# SDuino_ultramicroOLED_Dual.net
KiCad netlist of a schematic drawn in EAGLE
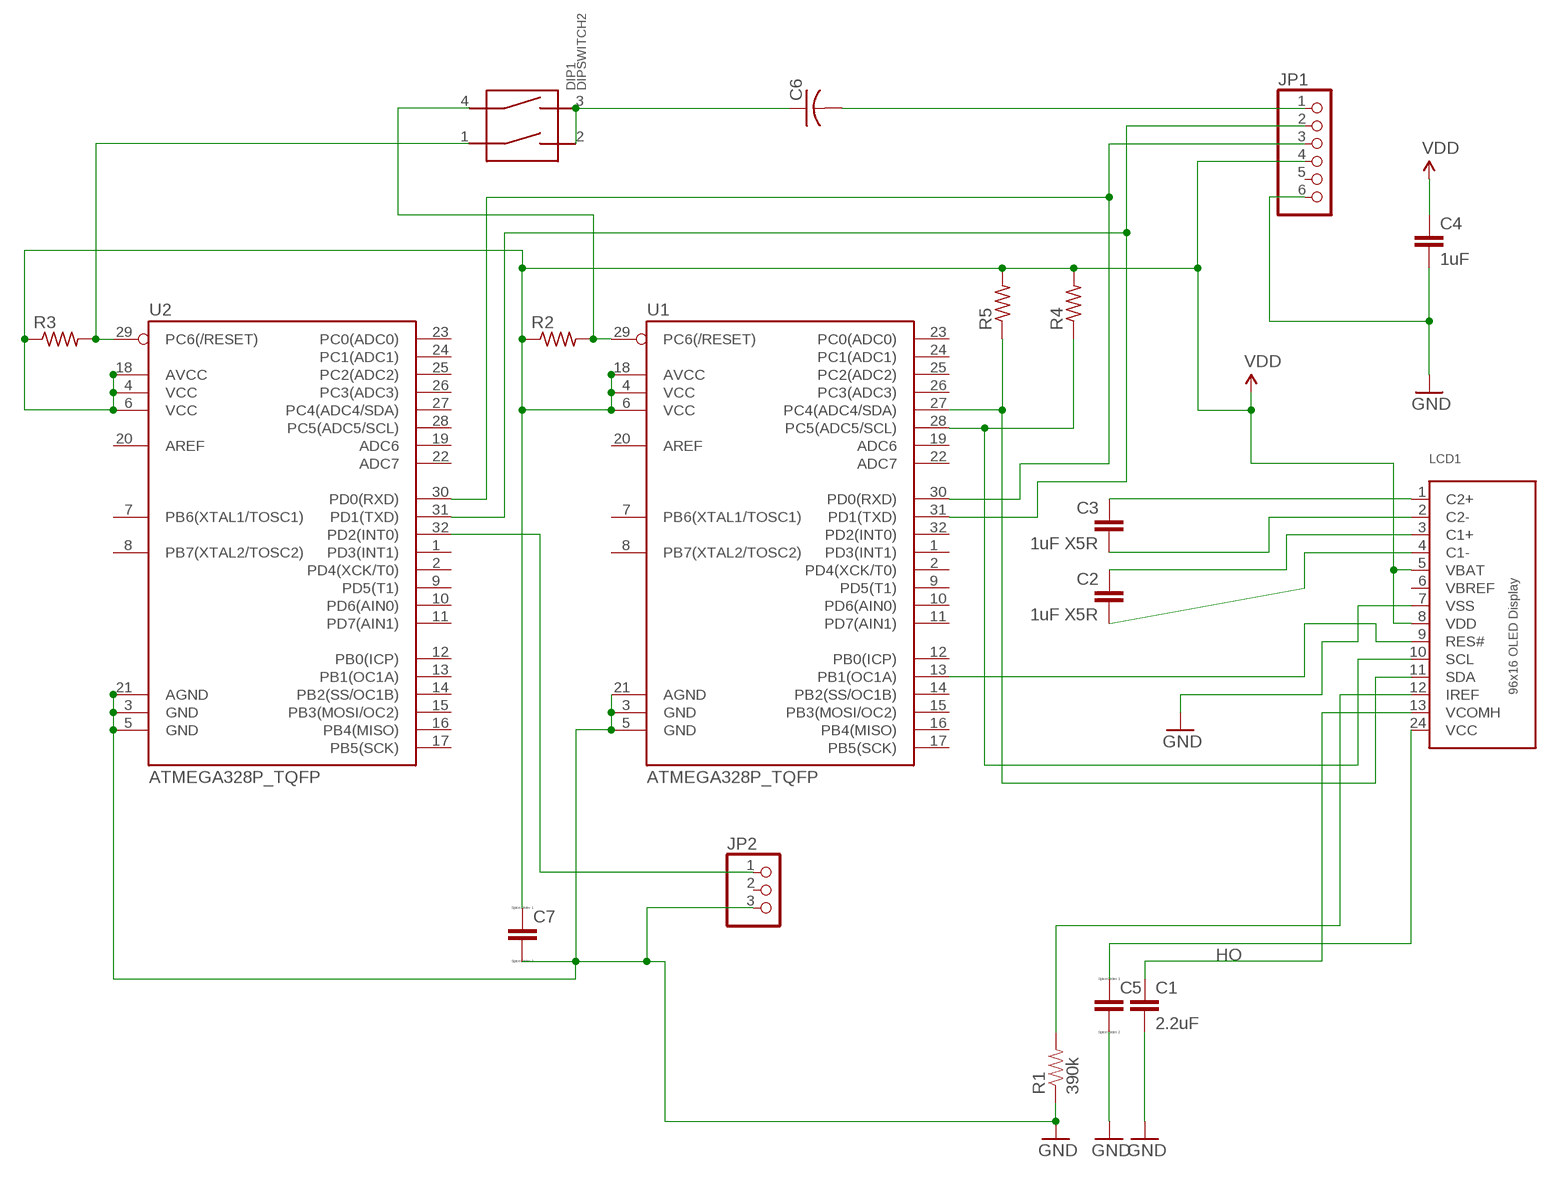
[diagram p0: schematic, sheet 1]

(export (version "E")
  (design (tool "Eeschema 10.0.6"))
  (components
    (comp (ref "C1")
      (value "2.2uF")
      (footprint "eagle-import:0805")
      (libsource (lib "eagle-import") (part "CAP0805"))
    )
    (comp (ref "C2")
      (value "1uF X5R")
      (footprint "eagle-import:0805")
      (libsource (lib "eagle-import") (part "CAP0805"))
    )
    (comp (ref "C3")
      (value "1uF X5R")
      (footprint "eagle-import:0805")
      (libsource (lib "eagle-import") (part "CAP0805"))
    )
    (comp (ref "C4")
      (value "1uF")
      (footprint "eagle-import:0603-CAP")
      (libsource (lib "eagle-import") (part "CAP0603-CAP"))
    )
    (comp (ref "C5")
      (value "CC0603")
      (footprint "eagle-import:C0603")
      (libsource (lib "eagle-import") (part "CC0603"))
    )
    (comp (ref "C6")
      (value "C-USC0603K")
      (footprint "eagle-import:C0603K")
      (libsource (lib "eagle-import") (part "C-USC0603K"))
    )
    (comp (ref "C7")
      (value "CC0603")
      (footprint "eagle-import:C0603")
      (libsource (lib "eagle-import") (part "CC0603"))
    )
    (comp (ref "DIP1")
      (value "DIPSWITCH2")
      (footprint "eagle-import:DIPSWITCH2")
      (libsource (lib "eagle-import") (part "DIPSWITCH2"))
    )
    (comp (ref "JP1")
      (value "HEADER-1X6")
      (footprint "eagle-import:1X06_OVAL")
      (libsource (lib "eagle-import") (part "HEADER-1X6"))
    )
    (comp (ref "JP2")
      (value "HEADER-1X3")
      (footprint "eagle-import:1X03_OVAL")
      (libsource (lib "eagle-import") (part "HEADER-1X3"))
    )
    (comp (ref "LCD1")
      (value "DISP_OLED_UG-9616GLBBG02")
      (footprint "eagle-import:UG-9616GLBBG02_0.65MM_WRAPAROUND")
      (libsource (lib "eagle-import") (part "DISP_OLED_UG-9616GLBBG02"))
    )
    (comp (ref "R1")
      (value "390k")
      (footprint "eagle-import:0603-RES")
      (libsource (lib "eagle-import") (part "RESISTOR0603-RES"))
    )
    (comp (ref "R2")
      (value "R-US_R0603")
      (footprint "eagle-import:R0603")
      (libsource (lib "eagle-import") (part "R-US_R0603"))
    )
    (comp (ref "R3")
      (value "R-US_R0603")
      (footprint "eagle-import:R0603")
      (libsource (lib "eagle-import") (part "R-US_R0603"))
    )
    (comp (ref "R4")
      (value "R-US_R0603")
      (footprint "eagle-import:R0603")
      (libsource (lib "eagle-import") (part "R-US_R0603"))
    )
    (comp (ref "R5")
      (value "R-US_R0603")
      (footprint "eagle-import:R0603")
      (libsource (lib "eagle-import") (part "R-US_R0603"))
    )
    (comp (ref "U1")
      (value "ATMEGA328P_TQFP")
      (footprint "eagle-import:TQFP32-08")
      (libsource (lib "eagle-import") (part "ATMEGA328P_TQFP"))
    )
    (comp (ref "U2")
      (value "ATMEGA328P_TQFP")
      (footprint "eagle-import:TQFP32-08")
      (libsource (lib "eagle-import") (part "ATMEGA328P_TQFP"))
    )
  )
  (nets
    (net (code "1") (name "/HO") (class "Default")
      (node (ref "C1") (pin "1") (pinfunction "1_1") (pintype "passive"))
      (node (ref "LCD1") (pin "13") (pinfunction "VCOMH_13") (pintype "bidirectional"))
    )
    (net (code "2") (name "GND") (class "Default")
      (node (ref "C1") (pin "2") (pinfunction "2_2") (pintype "passive"))
      (node (ref "C4") (pin "2") (pinfunction "2_2") (pintype "passive"))
      (node (ref "C5") (pin "2") (pinfunction "2_2") (pintype "passive"))
      (node (ref "C7") (pin "2") (pinfunction "2_2") (pintype "passive"))
      (node (ref "JP1") (pin "6") (pinfunction "6_6") (pintype "passive"))
      (node (ref "JP2") (pin "3") (pinfunction "3_3") (pintype "passive"))
      (node (ref "LCD1") (pin "7") (pinfunction "VSS_7") (pintype "bidirectional"))
      (node (ref "R1") (pin "1") (pinfunction "1_1") (pintype "passive"))
      (node (ref "U1") (pin "21") (pinfunction "AGND_21") (pintype "bidirectional"))
      (node (ref "U1") (pin "3") (pinfunction "GND_3") (pintype "bidirectional"))
      (node (ref "U1") (pin "5") (pinfunction "GND_5") (pintype "bidirectional"))
      (node (ref "U2") (pin "21") (pinfunction "AGND_21") (pintype "bidirectional"))
      (node (ref "U2") (pin "3") (pinfunction "GND_3") (pintype "bidirectional"))
      (node (ref "U2") (pin "5") (pinfunction "GND_5") (pintype "bidirectional"))
    )
    (net (code "3") (name "Net-(C6-Pad2)") (class "Default")
      (node (ref "C6") (pin "2") (pinfunction "2_2") (pintype "passive"))
      (node (ref "JP1") (pin "1") (pinfunction "1_1") (pintype "passive"))
    )
    (net (code "4") (name "Net-(DIP1-P$1)") (class "Default")
      (node (ref "DIP1") (pin "1") (pinfunction "P$1_1") (pintype "bidirectional"))
      (node (ref "R3") (pin "2") (pinfunction "2_2") (pintype "passive"))
      (node (ref "U2") (pin "29") (pinfunction "PC6(/RESET)_29") (pintype "bidirectional"))
    )
    (net (code "5") (name "Net-(DIP1-P$2)") (class "Default")
      (node (ref "C6") (pin "1") (pinfunction "1_1") (pintype "passive"))
      (node (ref "DIP1") (pin "2") (pinfunction "P$2_2") (pintype "bidirectional"))
      (node (ref "DIP1") (pin "3") (pinfunction "P$3_3") (pintype "bidirectional"))
    )
    (net (code "6") (name "Net-(DIP1-P$4)") (class "Default")
      (node (ref "DIP1") (pin "4") (pinfunction "P$4_4") (pintype "bidirectional"))
      (node (ref "R2") (pin "2") (pinfunction "2_2") (pintype "passive"))
      (node (ref "U1") (pin "29") (pinfunction "PC6(/RESET)_29") (pintype "bidirectional"))
    )
    (net (code "7") (name "Net-(LCD1-C1+)") (class "Default")
      (node (ref "C2") (pin "1") (pinfunction "1_1") (pintype "passive"))
      (node (ref "LCD1") (pin "3") (pinfunction "C1+_3") (pintype "bidirectional"))
    )
    (net (code "8") (name "Net-(LCD1-C1-)") (class "Default")
      (node (ref "C2") (pin "2") (pinfunction "2_2") (pintype "passive"))
      (node (ref "LCD1") (pin "4") (pinfunction "C1-_4") (pintype "bidirectional"))
    )
    (net (code "9") (name "Net-(LCD1-C2+)") (class "Default")
      (node (ref "C3") (pin "1") (pinfunction "1_1") (pintype "passive"))
      (node (ref "LCD1") (pin "1") (pinfunction "C2+_1") (pintype "bidirectional"))
    )
    (net (code "10") (name "Net-(LCD1-C2-)") (class "Default")
      (node (ref "C3") (pin "2") (pinfunction "2_2") (pintype "passive"))
      (node (ref "LCD1") (pin "2") (pinfunction "C2-_2") (pintype "bidirectional"))
    )
    (net (code "11") (name "Net-(LCD1-IREF)") (class "Default")
      (node (ref "LCD1") (pin "12") (pinfunction "IREF_12") (pintype "bidirectional"))
      (node (ref "R1") (pin "2") (pinfunction "2_2") (pintype "passive"))
    )
    (net (code "12") (name "Net-(LCD1-RES#)") (class "Default")
      (node (ref "LCD1") (pin "9") (pinfunction "RES#_9") (pintype "bidirectional"))
      (node (ref "U1") (pin "13") (pinfunction "PB1(OC1A)_13") (pintype "bidirectional"))
    )
    (net (code "13") (name "Net-(LCD1-SCL)") (class "Default")
      (node (ref "LCD1") (pin "10") (pinfunction "SCL_10") (pintype "bidirectional"))
      (node (ref "R4") (pin "1") (pinfunction "1_1") (pintype "passive"))
      (node (ref "U1") (pin "28") (pinfunction "PC5(ADC5/SCL)_28") (pintype "bidirectional"))
    )
    (net (code "14") (name "Net-(LCD1-SDA)") (class "Default")
      (node (ref "LCD1") (pin "11") (pinfunction "SDA_11") (pintype "bidirectional"))
      (node (ref "R5") (pin "1") (pinfunction "1_1") (pintype "passive"))
      (node (ref "U1") (pin "27") (pinfunction "PC4(ADC4/SDA)_27") (pintype "bidirectional"))
    )
    (net (code "15") (name "Net-(LCD1-VCC)") (class "Default")
      (node (ref "C5") (pin "1") (pinfunction "1_1") (pintype "passive"))
      (node (ref "LCD1") (pin "24") (pinfunction "VCC_24") (pintype "bidirectional"))
    )
    (net (code "16") (name "Net-(U1-PD0(RXD))") (class "Default")
      (node (ref "JP1") (pin "3") (pinfunction "3_3") (pintype "passive"))
      (node (ref "U1") (pin "30") (pinfunction "PD0(RXD)_30") (pintype "bidirectional"))
      (node (ref "U2") (pin "30") (pinfunction "PD0(RXD)_30") (pintype "bidirectional"))
    )
    (net (code "17") (name "Net-(U1-PD1(TXD))") (class "Default")
      (node (ref "JP1") (pin "2") (pinfunction "2_2") (pintype "passive"))
      (node (ref "U1") (pin "31") (pinfunction "PD1(TXD)_31") (pintype "bidirectional"))
      (node (ref "U2") (pin "31") (pinfunction "PD1(TXD)_31") (pintype "bidirectional"))
    )
    (net (code "18") (name "Net-(U2-PD2(INT0))") (class "Default")
      (node (ref "JP2") (pin "1") (pinfunction "1_1") (pintype "passive"))
      (node (ref "U2") (pin "32") (pinfunction "PD2(INT0)_32") (pintype "bidirectional"))
    )
    (net (code "19") (name "VDD") (class "Default")
      (node (ref "C4") (pin "1") (pinfunction "1_1") (pintype "passive"))
      (node (ref "C7") (pin "1") (pinfunction "1_1") (pintype "passive"))
      (node (ref "JP1") (pin "4") (pinfunction "4_4") (pintype "passive"))
      (node (ref "LCD1") (pin "5") (pinfunction "VBAT_5") (pintype "bidirectional"))
      (node (ref "LCD1") (pin "8") (pinfunction "VDD_8") (pintype "bidirectional"))
      (node (ref "R2") (pin "1") (pinfunction "1_1") (pintype "passive"))
      (node (ref "R3") (pin "1") (pinfunction "1_1") (pintype "passive"))
      (node (ref "R4") (pin "2") (pinfunction "2_2") (pintype "passive"))
      (node (ref "R5") (pin "2") (pinfunction "2_2") (pintype "passive"))
      (node (ref "U1") (pin "18") (pinfunction "AVCC_18") (pintype "bidirectional"))
      (node (ref "U1") (pin "4") (pinfunction "VCC_4") (pintype "bidirectional"))
      (node (ref "U1") (pin "6") (pinfunction "VCC_6") (pintype "bidirectional"))
      (node (ref "U2") (pin "18") (pinfunction "AVCC_18") (pintype "bidirectional"))
      (node (ref "U2") (pin "4") (pinfunction "VCC_4") (pintype "bidirectional"))
      (node (ref "U2") (pin "6") (pinfunction "VCC_6") (pintype "bidirectional"))
    )
    (net (code "20") (name "unconnected-(JP1-Pad5)") (class "Default")
      (node (ref "JP1") (pin "5") (pinfunction "5_5") (pintype "passive"))
    )
    (net (code "21") (name "unconnected-(JP2-Pad2)") (class "Default")
      (node (ref "JP2") (pin "2") (pinfunction "2_2") (pintype "passive"))
    )
    (net (code "22") (name "unconnected-(LCD1-VBREF-Pad6)") (class "Default")
      (node (ref "LCD1") (pin "6") (pinfunction "VBREF_6") (pintype "bidirectional"))
    )
    (net (code "23") (name "unconnected-(U1-ADC6-Pad19)") (class "Default")
      (node (ref "U1") (pin "19") (pinfunction "ADC6_19") (pintype "bidirectional"))
    )
    (net (code "24") (name "unconnected-(U1-ADC7-Pad22)") (class "Default")
      (node (ref "U1") (pin "22") (pinfunction "ADC7_22") (pintype "bidirectional"))
    )
    (net (code "25") (name "unconnected-(U1-AREF-Pad20)") (class "Default")
      (node (ref "U1") (pin "20") (pinfunction "AREF_20") (pintype "bidirectional"))
    )
    (net (code "26") (name "unconnected-(U1-PB0(ICP)-Pad12)") (class "Default")
      (node (ref "U1") (pin "12") (pinfunction "PB0(ICP)_12") (pintype "bidirectional"))
    )
    (net (code "27") (name "unconnected-(U1-PB2(SS{slash}OC1B)-Pad14)") (class "Default")
      (node (ref "U1") (pin "14") (pinfunction "PB2(SS/OC1B)_14") (pintype "bidirectional"))
    )
    (net (code "28") (name "unconnected-(U1-PB3(MOSI{slash}OC2)-Pad15)") (class "Default")
      (node (ref "U1") (pin "15") (pinfunction "PB3(MOSI/OC2)_15") (pintype "bidirectional"))
    )
    (net (code "29") (name "unconnected-(U1-PB4(MISO)-Pad16)") (class "Default")
      (node (ref "U1") (pin "16") (pinfunction "PB4(MISO)_16") (pintype "bidirectional"))
    )
    (net (code "30") (name "unconnected-(U1-PB5(SCK)-Pad17)") (class "Default")
      (node (ref "U1") (pin "17") (pinfunction "PB5(SCK)_17") (pintype "bidirectional"))
    )
    (net (code "31") (name "unconnected-(U1-PB6(XTAL1{slash}TOSC1)-Pad7)") (class "Default")
      (node (ref "U1") (pin "7") (pinfunction "PB6(XTAL1/TOSC1)_7") (pintype "bidirectional"))
    )
    (net (code "32") (name "unconnected-(U1-PB7(XTAL2{slash}TOSC2)-Pad8)") (class "Default")
      (node (ref "U1") (pin "8") (pinfunction "PB7(XTAL2/TOSC2)_8") (pintype "bidirectional"))
    )
    (net (code "33") (name "unconnected-(U1-PC0(ADC0)-Pad23)") (class "Default")
      (node (ref "U1") (pin "23") (pinfunction "PC0(ADC0)_23") (pintype "bidirectional"))
    )
    (net (code "34") (name "unconnected-(U1-PC1(ADC1)-Pad24)") (class "Default")
      (node (ref "U1") (pin "24") (pinfunction "PC1(ADC1)_24") (pintype "bidirectional"))
    )
    (net (code "35") (name "unconnected-(U1-PC2(ADC2)-Pad25)") (class "Default")
      (node (ref "U1") (pin "25") (pinfunction "PC2(ADC2)_25") (pintype "bidirectional"))
    )
    (net (code "36") (name "unconnected-(U1-PC3(ADC3)-Pad26)") (class "Default")
      (node (ref "U1") (pin "26") (pinfunction "PC3(ADC3)_26") (pintype "bidirectional"))
    )
    (net (code "37") (name "unconnected-(U1-PD2(INT0)-Pad32)") (class "Default")
      (node (ref "U1") (pin "32") (pinfunction "PD2(INT0)_32") (pintype "bidirectional"))
    )
    (net (code "38") (name "unconnected-(U1-PD3(INT1)-Pad1)") (class "Default")
      (node (ref "U1") (pin "1") (pinfunction "PD3(INT1)_1") (pintype "bidirectional"))
    )
    (net (code "39") (name "unconnected-(U1-PD4(XCK{slash}T0)-Pad2)") (class "Default")
      (node (ref "U1") (pin "2") (pinfunction "PD4(XCK/T0)_2") (pintype "bidirectional"))
    )
    (net (code "40") (name "unconnected-(U1-PD5(T1)-Pad9)") (class "Default")
      (node (ref "U1") (pin "9") (pinfunction "PD5(T1)_9") (pintype "bidirectional"))
    )
    (net (code "41") (name "unconnected-(U1-PD6(AIN0)-Pad10)") (class "Default")
      (node (ref "U1") (pin "10") (pinfunction "PD6(AIN0)_10") (pintype "bidirectional"))
    )
    (net (code "42") (name "unconnected-(U1-PD7(AIN1)-Pad11)") (class "Default")
      (node (ref "U1") (pin "11") (pinfunction "PD7(AIN1)_11") (pintype "bidirectional"))
    )
    (net (code "43") (name "unconnected-(U2-ADC6-Pad19)") (class "Default")
      (node (ref "U2") (pin "19") (pinfunction "ADC6_19") (pintype "bidirectional"))
    )
    (net (code "44") (name "unconnected-(U2-ADC7-Pad22)") (class "Default")
      (node (ref "U2") (pin "22") (pinfunction "ADC7_22") (pintype "bidirectional"))
    )
    (net (code "45") (name "unconnected-(U2-AREF-Pad20)") (class "Default")
      (node (ref "U2") (pin "20") (pinfunction "AREF_20") (pintype "bidirectional"))
    )
    (net (code "46") (name "unconnected-(U2-PB0(ICP)-Pad12)") (class "Default")
      (node (ref "U2") (pin "12") (pinfunction "PB0(ICP)_12") (pintype "bidirectional"))
    )
    (net (code "47") (name "unconnected-(U2-PB1(OC1A)-Pad13)") (class "Default")
      (node (ref "U2") (pin "13") (pinfunction "PB1(OC1A)_13") (pintype "bidirectional"))
    )
    (net (code "48") (name "unconnected-(U2-PB2(SS{slash}OC1B)-Pad14)") (class "Default")
      (node (ref "U2") (pin "14") (pinfunction "PB2(SS/OC1B)_14") (pintype "bidirectional"))
    )
    (net (code "49") (name "unconnected-(U2-PB3(MOSI{slash}OC2)-Pad15)") (class "Default")
      (node (ref "U2") (pin "15") (pinfunction "PB3(MOSI/OC2)_15") (pintype "bidirectional"))
    )
    (net (code "50") (name "unconnected-(U2-PB4(MISO)-Pad16)") (class "Default")
      (node (ref "U2") (pin "16") (pinfunction "PB4(MISO)_16") (pintype "bidirectional"))
    )
    (net (code "51") (name "unconnected-(U2-PB5(SCK)-Pad17)") (class "Default")
      (node (ref "U2") (pin "17") (pinfunction "PB5(SCK)_17") (pintype "bidirectional"))
    )
    (net (code "52") (name "unconnected-(U2-PB6(XTAL1{slash}TOSC1)-Pad7)") (class "Default")
      (node (ref "U2") (pin "7") (pinfunction "PB6(XTAL1/TOSC1)_7") (pintype "bidirectional"))
    )
    (net (code "53") (name "unconnected-(U2-PB7(XTAL2{slash}TOSC2)-Pad8)") (class "Default")
      (node (ref "U2") (pin "8") (pinfunction "PB7(XTAL2/TOSC2)_8") (pintype "bidirectional"))
    )
    (net (code "54") (name "unconnected-(U2-PC0(ADC0)-Pad23)") (class "Default")
      (node (ref "U2") (pin "23") (pinfunction "PC0(ADC0)_23") (pintype "bidirectional"))
    )
    (net (code "55") (name "unconnected-(U2-PC1(ADC1)-Pad24)") (class "Default")
      (node (ref "U2") (pin "24") (pinfunction "PC1(ADC1)_24") (pintype "bidirectional"))
    )
    (net (code "56") (name "unconnected-(U2-PC2(ADC2)-Pad25)") (class "Default")
      (node (ref "U2") (pin "25") (pinfunction "PC2(ADC2)_25") (pintype "bidirectional"))
    )
    (net (code "57") (name "unconnected-(U2-PC3(ADC3)-Pad26)") (class "Default")
      (node (ref "U2") (pin "26") (pinfunction "PC3(ADC3)_26") (pintype "bidirectional"))
    )
    (net (code "58") (name "unconnected-(U2-PC4(ADC4{slash}SDA)-Pad27)") (class "Default")
      (node (ref "U2") (pin "27") (pinfunction "PC4(ADC4/SDA)_27") (pintype "bidirectional"))
    )
    (net (code "59") (name "unconnected-(U2-PC5(ADC5{slash}SCL)-Pad28)") (class "Default")
      (node (ref "U2") (pin "28") (pinfunction "PC5(ADC5/SCL)_28") (pintype "bidirectional"))
    )
    (net (code "60") (name "unconnected-(U2-PD3(INT1)-Pad1)") (class "Default")
      (node (ref "U2") (pin "1") (pinfunction "PD3(INT1)_1") (pintype "bidirectional"))
    )
    (net (code "61") (name "unconnected-(U2-PD4(XCK{slash}T0)-Pad2)") (class "Default")
      (node (ref "U2") (pin "2") (pinfunction "PD4(XCK/T0)_2") (pintype "bidirectional"))
    )
    (net (code "62") (name "unconnected-(U2-PD5(T1)-Pad9)") (class "Default")
      (node (ref "U2") (pin "9") (pinfunction "PD5(T1)_9") (pintype "bidirectional"))
    )
    (net (code "63") (name "unconnected-(U2-PD6(AIN0)-Pad10)") (class "Default")
      (node (ref "U2") (pin "10") (pinfunction "PD6(AIN0)_10") (pintype "bidirectional"))
    )
    (net (code "64") (name "unconnected-(U2-PD7(AIN1)-Pad11)") (class "Default")
      (node (ref "U2") (pin "11") (pinfunction "PD7(AIN1)_11") (pintype "bidirectional"))
    )
  )
)
